# sch_station_de_charge_r.net
KiCad netlist of a schematic drawn in Altium Designer
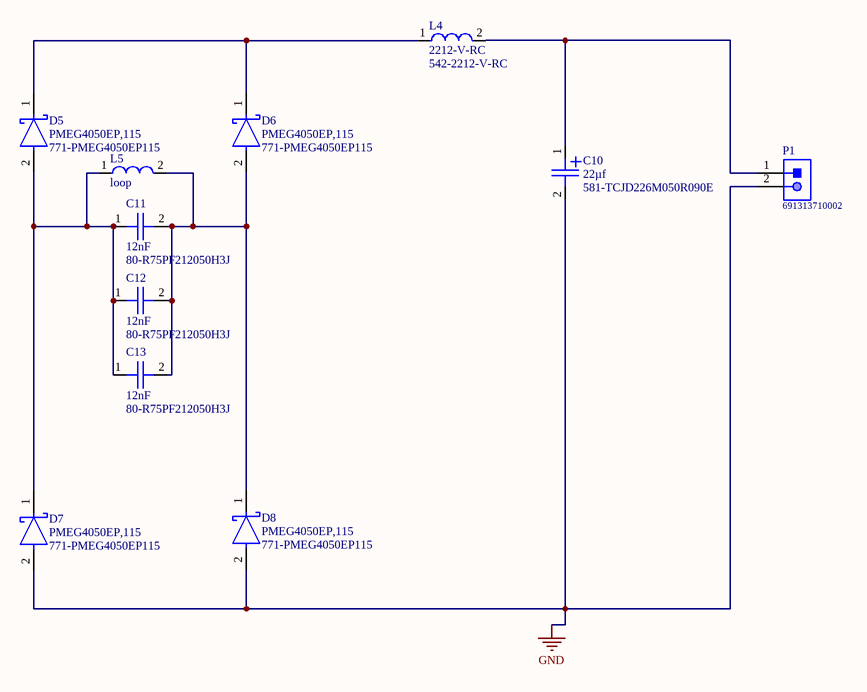
[diagram p0: sch_station_de_charge_r.SchDoc]

(export (version "E")
  (design (tool "Eeschema 10.0.6"))
  (components
    (comp (ref "C10")
      (value "22µf")
      (footprint "CAPPM7343X310N")
      (fields
        (field (name "MANUFACTURER") "Kyocera AVX")
        (field (name "MANUFACTURER PART NUMBER") "TCJD226M050R0090E")
        (field (name "SUPPLIER PART NUMBER 1") "581-TCJD226M050R090E")
      )
      (libsource (lib "station_de_charge_SchLib") (part "TCJD226M050R0090E"))
    )
    (comp (ref "C11")
      (value "12nF")
      (footprint "R75PF212050H3J")
      (description "Cap Film 0.012uF 630V PP 5% Molded Solder Pin 10mm 125°C Bulk")
      (fields
        (field (name "MANUFACTURER") "KEMET")
        (field (name "MANUFACTURER PART NUMBER") "R75PF212050H3J")
        (field (name "SUPPLIER PART NUMBER 1") "80-R75PF212050H3J")
      )
      (libsource (lib "station_de_charge_SchLib") (part "R75PF212050H3J"))
    )
    (comp (ref "C12")
      (value "12nF")
      (footprint "R75PF212050H3J")
      (description "Cap Film 0.012uF 630V PP 5% Molded Solder Pin 10mm 125°C Bulk")
      (fields
        (field (name "MANUFACTURER") "KEMET")
        (field (name "MANUFACTURER PART NUMBER") "R75PF212050H3J")
        (field (name "SUPPLIER PART NUMBER 1") "80-R75PF212050H3J")
      )
      (libsource (lib "station_de_charge_SchLib") (part "R75PF212050H3J"))
    )
    (comp (ref "C13")
      (value "12nF")
      (footprint "R75PF212050H3J")
      (description "Cap Film 0.012uF 630V PP 5% Molded Solder Pin 10mm 125°C Bulk")
      (fields
        (field (name "MANUFACTURER") "KEMET")
        (field (name "MANUFACTURER PART NUMBER") "R75PF212050H3J")
        (field (name "SUPPLIER PART NUMBER 1") "80-R75PF212050H3J")
      )
      (libsource (lib "station_de_charge_SchLib") (part "R75PF212050H3J"))
    )
    (comp (ref "D5")
      (value "PMEG4050EP,115")
      (footprint "FP-SOD128-MFG")
      (description "DIODE SCHOTTKY 40V 5A SOD128")
      (fields
        (field (name "MANUFACTURER") "Nexperia")
        (field (name "SUPPLIER PART NUMBER 1") "771-PMEG4050EP115")
      )
      (libsource (lib "station_de_charge_SchLib") (part "PMEG4050EP,115"))
    )
    (comp (ref "D6")
      (value "PMEG4050EP,115")
      (footprint "FP-SOD128-MFG")
      (description "DIODE SCHOTTKY 40V 5A SOD128")
      (fields
        (field (name "MANUFACTURER") "Nexperia")
        (field (name "SUPPLIER PART NUMBER 1") "771-PMEG4050EP115")
      )
      (libsource (lib "station_de_charge_SchLib") (part "PMEG4050EP,115"))
    )
    (comp (ref "D7")
      (value "PMEG4050EP,115")
      (footprint "FP-SOD128-MFG")
      (description "DIODE SCHOTTKY 40V 5A SOD128")
      (fields
        (field (name "MANUFACTURER") "Nexperia")
        (field (name "SUPPLIER PART NUMBER 1") "771-PMEG4050EP115")
      )
      (libsource (lib "station_de_charge_SchLib") (part "PMEG4050EP,115"))
    )
    (comp (ref "D8")
      (value "PMEG4050EP,115")
      (footprint "FP-SOD128-MFG")
      (description "DIODE SCHOTTKY 40V 5A SOD128")
      (fields
        (field (name "MANUFACTURER") "Nexperia")
        (field (name "SUPPLIER PART NUMBER 1") "771-PMEG4050EP115")
      )
      (libsource (lib "station_de_charge_SchLib") (part "PMEG4050EP,115"))
    )
    (comp (ref "L4")
      (value "2212-V-RC")
      (footprint "IND_HCTI-220-5.8")
      (description "Inductor High Current Toroid 100uH/64uH 15% 1KHz 4.4A 56mOhm DCR RDL")
      (fields
        (field (name "MANUFACTURER") "Bourns JW Miller")
        (field (name "TOLERANCE") "15%")
        (field (name "SUPPLIER PART NUMBER 1") "542-2212-V-RC")
      )
      (libsource (lib "station_de_charge_SchLib") (part "2212-V-RC"))
    )
    (comp (ref "L5")
      (value "loop")
      (footprint "loop")
      (libsource (lib "station_de_charge_SchLib") (part "loop"))
    )
    (comp (ref "P1")
      (value "691313710002")
      (footprint "691313710002")
      (description "Serie 3137 - 5.00mm Close Horizontal PCB Header WR-TBL, 2 pin")
      (fields (field (name "MANUFACTURER") "Wurth Elektronik") (field (name "PUBLISHER") "WurthElektronik"))
      (libsource (lib "station_de_charge_SchLib") (part "CMP-1502-02048-1"))
    )
  )
  (nets
    (net (code "1") (name "GND") (class "Default")
      (node (ref "C10") (pin "2") (pinfunction "2_2") (pintype "passive"))
      (node (ref "D7") (pin "2") (pinfunction "A_2") (pintype "passive"))
      (node (ref "D8") (pin "2") (pinfunction "A_2") (pintype "passive"))
      (node (ref "P1") (pin "2") (pinfunction "2_2") (pintype "passive"))
    )
    (net (code "2") (name "Net-(C10-Pad1)") (class "Default")
      (node (ref "C10") (pin "1") (pinfunction "1_1") (pintype "passive"))
      (node (ref "L4") (pin "2") (pinfunction "2_2") (pintype "passive"))
      (node (ref "P1") (pin "1") (pinfunction "1_1") (pintype "passive"))
    )
    (net (code "3") (name "Net-(D5-A)") (class "Default")
      (node (ref "C11") (pin "1") (pinfunction "1_1") (pintype "passive"))
      (node (ref "C12") (pin "1") (pinfunction "1_1") (pintype "passive"))
      (node (ref "C13") (pin "1") (pinfunction "1_1") (pintype "passive"))
      (node (ref "D5") (pin "2") (pinfunction "A_2") (pintype "passive"))
      (node (ref "D7") (pin "1") (pinfunction "K_1") (pintype "passive"))
      (node (ref "L5") (pin "1") (pinfunction "1_1") (pintype "passive"))
    )
    (net (code "4") (name "Net-(D5-K)") (class "Default")
      (node (ref "D5") (pin "1") (pinfunction "K_1") (pintype "passive"))
      (node (ref "D6") (pin "1") (pinfunction "K_1") (pintype "passive"))
      (node (ref "L4") (pin "1") (pinfunction "1_1") (pintype "passive"))
    )
    (net (code "5") (name "Net-(D6-A)") (class "Default")
      (node (ref "C11") (pin "2") (pinfunction "2_2") (pintype "passive"))
      (node (ref "C12") (pin "2") (pinfunction "2_2") (pintype "passive"))
      (node (ref "C13") (pin "2") (pinfunction "2_2") (pintype "passive"))
      (node (ref "D6") (pin "2") (pinfunction "A_2") (pintype "passive"))
      (node (ref "D8") (pin "1") (pinfunction "K_1") (pintype "passive"))
      (node (ref "L5") (pin "2") (pinfunction "2_2") (pintype "passive"))
    )
  )
)
